# design.net
KiCad netlist of a schematic drawn in Altium Designer
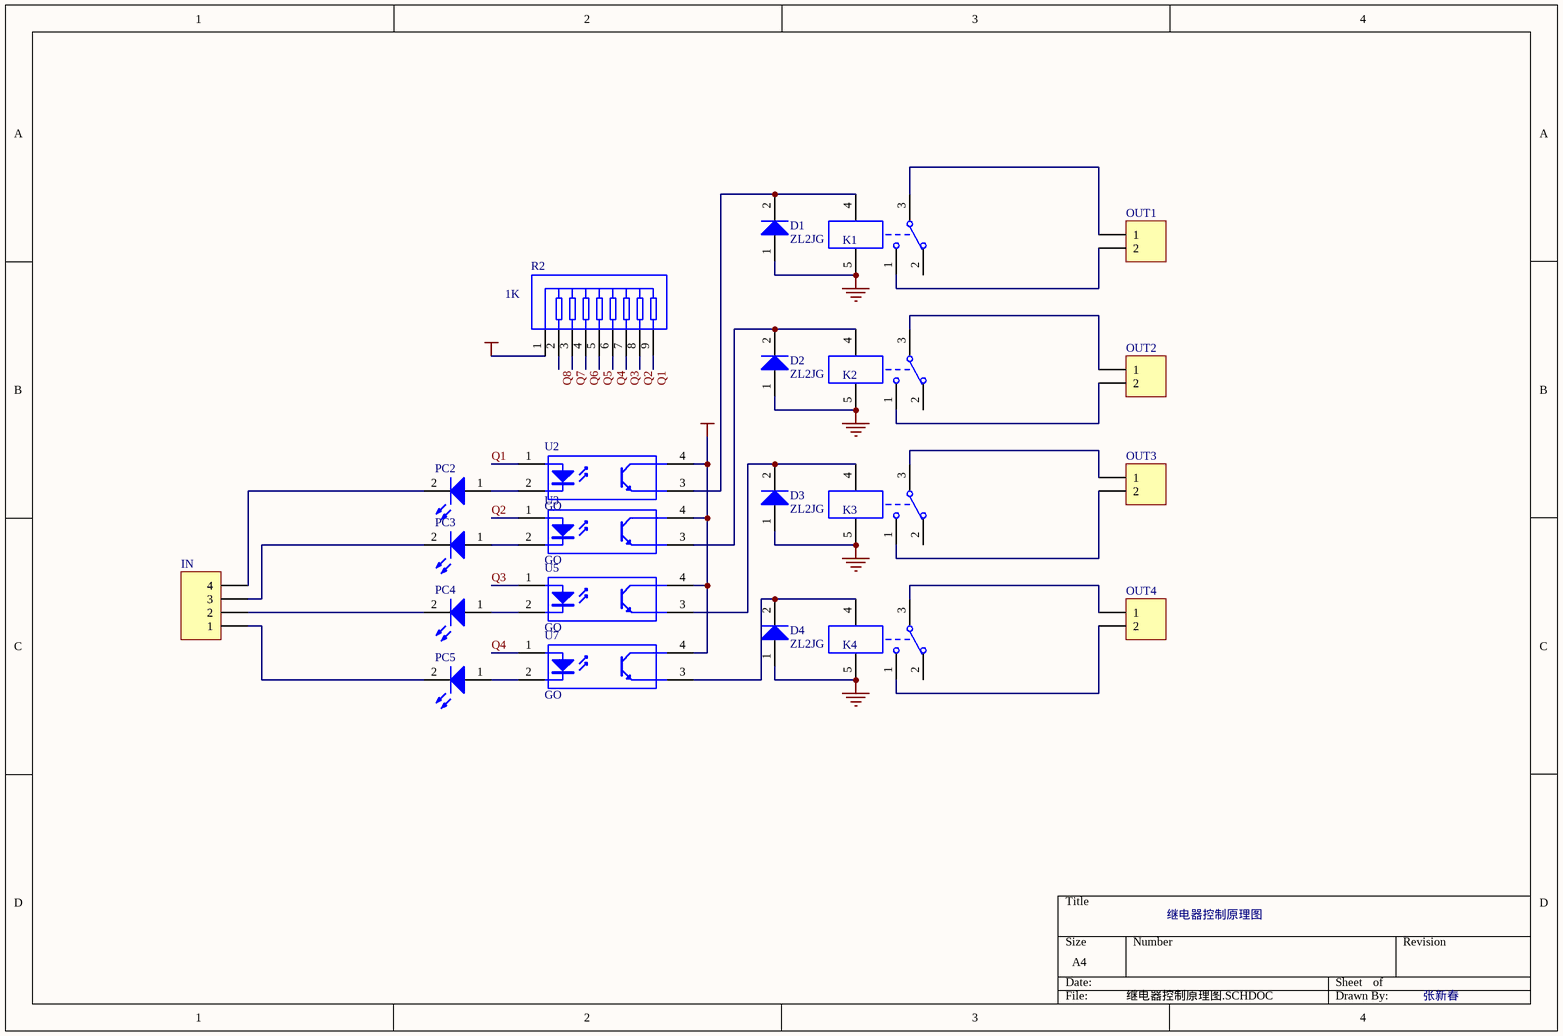
[diagram p0: 继电器控制原理图.SCHDOC]

(export (version "E")
  (design (tool "Eeschema 10.0.6"))
  (components
    (comp (ref "D1")
      (value "ZL2JG")
      (footprint "D-ZL-10")
      (description "整流二极管")
      (fields (field (name "PUBLISHER") "Altium Limited"))
      (libsource (lib "zxcourhc") (part "ZL2JG"))
    )
    (comp (ref "D2")
      (value "ZL2JG")
      (footprint "D-ZL-10")
      (description "整流二极管")
      (fields (field (name "PUBLISHER") "Altium Limited"))
      (libsource (lib "zxcourhc") (part "ZL2JG"))
    )
    (comp (ref "D3")
      (value "ZL2JG")
      (footprint "D-ZL-10")
      (description "整流二极管")
      (fields (field (name "PUBLISHER") "Altium Limited"))
      (libsource (lib "zxcourhc") (part "ZL2JG"))
    )
    (comp (ref "D4")
      (value "ZL2JG")
      (footprint "D-ZL-10")
      (description "整流二极管")
      (fields (field (name "PUBLISHER") "Altium Limited"))
      (libsource (lib "zxcourhc") (part "ZL2JG"))
    )
    (comp (ref "IN")
      (value "Header 4")
      (footprint "HDR1X4")
      (description "Header, 4-Pin")
      (fields (field (name "PUBLISHER") "Altium Limited"))
      (libsource (lib "Miscellaneous Connectors") (part "Header 4"))
    )
    (comp (ref "K1")
      (value "JDQYCK")
      (footprint "JQC-3F/T73")
      (description "继电器——1常开1常闭")
      (fields (field (name "PUBLISHER") "Altium Limited"))
      (libsource (lib "zxcourhc") (part "JDQYCK"))
    )
    (comp (ref "K2")
      (value "JDQYCK")
      (footprint "JQC-3F/T73")
      (description "继电器——1常开1常闭")
      (fields (field (name "PUBLISHER") "Altium Limited"))
      (libsource (lib "zxcourhc") (part "JDQYCK"))
    )
    (comp (ref "K3")
      (value "JDQYCK")
      (footprint "JQC-3F/T73")
      (description "继电器——1常开1常闭")
      (fields (field (name "PUBLISHER") "Altium Limited"))
      (libsource (lib "zxcourhc") (part "JDQYCK"))
    )
    (comp (ref "K4")
      (value "JDQYCK")
      (footprint "JQC-3F/T73")
      (description "继电器——1常开1常闭")
      (fields (field (name "PUBLISHER") "Altium Limited"))
      (libsource (lib "zxcourhc") (part "JDQYCK"))
    )
    (comp (ref "OUT1")
      (value "PZ_2")
      (footprint "DYDZ")
      (description "排针——2")
      (fields (field (name "PUBLISHER") "Altium Limited"))
      (libsource (lib "zxcourhc") (part "PZ_2"))
    )
    (comp (ref "OUT2")
      (value "PZ_2")
      (footprint "DYDZ")
      (description "排针——2")
      (fields (field (name "PUBLISHER") "Altium Limited"))
      (libsource (lib "zxcourhc") (part "PZ_2"))
    )
    (comp (ref "OUT3")
      (value "PZ_2")
      (footprint "DYDZ")
      (description "排针——2")
      (fields (field (name "PUBLISHER") "Altium Limited"))
      (libsource (lib "zxcourhc") (part "PZ_2"))
    )
    (comp (ref "OUT4")
      (value "PZ_2")
      (footprint "DYDZ")
      (description "排针——2")
      (fields (field (name "PUBLISHER") "Altium Limited"))
      (libsource (lib "zxcourhc") (part "PZ_2"))
    )
    (comp (ref "PC2")
      (value "~")
      (footprint "CPDR")
      (description "发光二极管")
      (fields (field (name "PUBLISHER") "Altium Limited"))
      (libsource (lib "zxcourhc") (part "LED"))
    )
    (comp (ref "PC3")
      (value "~")
      (footprint "CPDR")
      (description "发光二极管")
      (fields (field (name "PUBLISHER") "Altium Limited"))
      (libsource (lib "zxcourhc") (part "LED"))
    )
    (comp (ref "PC4")
      (value "~")
      (footprint "CPDR")
      (description "发光二极管")
      (fields (field (name "PUBLISHER") "Altium Limited"))
      (libsource (lib "zxcourhc") (part "LED"))
    )
    (comp (ref "PC5")
      (value "~")
      (footprint "CPDR")
      (description "发光二极管")
      (fields (field (name "PUBLISHER") "Altium Limited"))
      (libsource (lib "zxcourhc") (part "LED"))
    )
    (comp (ref "R2")
      (value "1K")
      (footprint "HDR-10")
      (description "8位排阻")
      (fields (field (name "PUBLISHER") "Altium Limited"))
      (libsource (lib "zxcourhc") (part "Res PZ_8"))
    )
    (comp (ref "U2")
      (value "GO")
      (footprint "DIP-4")
      (description "光耦")
      (fields (field (name "PUBLISHER") "Altium Limited"))
      (libsource (lib "zxcourhc") (part "GO"))
    )
    (comp (ref "U3")
      (value "GO")
      (footprint "DIP-4")
      (description "光耦")
      (fields (field (name "PUBLISHER") "Altium Limited"))
      (libsource (lib "zxcourhc") (part "GO"))
    )
    (comp (ref "U5")
      (value "GO")
      (footprint "DIP-4")
      (description "光耦")
      (fields (field (name "PUBLISHER") "Altium Limited"))
      (libsource (lib "zxcourhc") (part "GO"))
    )
    (comp (ref "U7")
      (value "GO")
      (footprint "DIP-4")
      (description "光耦")
      (fields (field (name "PUBLISHER") "Altium Limited"))
      (libsource (lib "zxcourhc") (part "GO"))
    )
  )
  (nets
    (net (code "1") (name "+12V") (class "Default")
      (node (ref "U2") (pin "4") (pinfunction "C_4") (pintype "passive"))
      (node (ref "U3") (pin "4") (pinfunction "C_4") (pintype "passive"))
      (node (ref "U5") (pin "4") (pinfunction "C_4") (pintype "passive"))
      (node (ref "U7") (pin "4") (pinfunction "C_4") (pintype "passive"))
    )
    (net (code "2") (name "/Q1") (class "Default")
      (node (ref "R2") (pin "9") (pinfunction "9_9") (pintype "passive"))
      (node (ref "U2") (pin "1") (pinfunction "A_1") (pintype "passive"))
    )
    (net (code "3") (name "/Q2") (class "Default")
      (node (ref "R2") (pin "8") (pinfunction "8_8") (pintype "passive"))
      (node (ref "U3") (pin "1") (pinfunction "A_1") (pintype "passive"))
    )
    (net (code "4") (name "/Q3") (class "Default")
      (node (ref "R2") (pin "7") (pinfunction "7_7") (pintype "passive"))
      (node (ref "U5") (pin "1") (pinfunction "A_1") (pintype "passive"))
    )
    (net (code "5") (name "/Q4") (class "Default")
      (node (ref "R2") (pin "6") (pinfunction "6_6") (pintype "passive"))
      (node (ref "U7") (pin "1") (pinfunction "A_1") (pintype "passive"))
    )
    (net (code "6") (name "/Q5") (class "Default")
      (node (ref "R2") (pin "5") (pinfunction "5_5") (pintype "passive"))
    )
    (net (code "7") (name "/Q6") (class "Default")
      (node (ref "R2") (pin "4") (pinfunction "4_4") (pintype "passive"))
    )
    (net (code "8") (name "/Q7") (class "Default")
      (node (ref "R2") (pin "3") (pinfunction "3_3") (pintype "passive"))
    )
    (net (code "9") (name "/Q8") (class "Default")
      (node (ref "R2") (pin "2") (pinfunction "2_2") (pintype "passive"))
    )
    (net (code "10") (name "GND") (class "Default")
      (node (ref "D1") (pin "1") (pinfunction "A_1") (pintype "passive"))
      (node (ref "D2") (pin "1") (pinfunction "A_1") (pintype "passive"))
      (node (ref "D3") (pin "1") (pinfunction "A_1") (pintype "passive"))
      (node (ref "D4") (pin "1") (pinfunction "A_1") (pintype "passive"))
      (node (ref "K1") (pin "5") (pinfunction "5_5") (pintype "passive"))
      (node (ref "K2") (pin "5") (pinfunction "5_5") (pintype "passive"))
      (node (ref "K3") (pin "5") (pinfunction "5_5") (pintype "passive"))
      (node (ref "K4") (pin "5") (pinfunction "5_5") (pintype "passive"))
    )
    (net (code "11") (name "Net-(D1-K)") (class "Default")
      (node (ref "D1") (pin "2") (pinfunction "K_2") (pintype "passive"))
      (node (ref "K1") (pin "4") (pinfunction "4_4") (pintype "passive"))
      (node (ref "U2") (pin "3") (pinfunction "E_3") (pintype "passive"))
    )
    (net (code "12") (name "Net-(D2-K)") (class "Default")
      (node (ref "D2") (pin "2") (pinfunction "K_2") (pintype "passive"))
      (node (ref "K2") (pin "4") (pinfunction "4_4") (pintype "passive"))
      (node (ref "U3") (pin "3") (pinfunction "E_3") (pintype "passive"))
    )
    (net (code "13") (name "Net-(D3-K)") (class "Default")
      (node (ref "D3") (pin "2") (pinfunction "K_2") (pintype "passive"))
      (node (ref "K3") (pin "4") (pinfunction "4_4") (pintype "passive"))
      (node (ref "U5") (pin "3") (pinfunction "E_3") (pintype "passive"))
    )
    (net (code "14") (name "Net-(D4-K)") (class "Default")
      (node (ref "D4") (pin "2") (pinfunction "K_2") (pintype "passive"))
      (node (ref "K4") (pin "4") (pinfunction "4_4") (pintype "passive"))
      (node (ref "U7") (pin "3") (pinfunction "E_3") (pintype "passive"))
    )
    (net (code "15") (name "Net-(K1-Pad1)") (class "Default")
      (node (ref "K1") (pin "1") (pinfunction "1_1") (pintype "passive"))
      (node (ref "OUT1") (pin "2") (pinfunction "2_2") (pintype "passive"))
    )
    (net (code "16") (name "Net-(K1-Pad3)") (class "Default")
      (node (ref "K1") (pin "3") (pinfunction "3_3") (pintype "passive"))
      (node (ref "OUT1") (pin "1") (pinfunction "1_1") (pintype "passive"))
    )
    (net (code "17") (name "Net-(K2-Pad1)") (class "Default")
      (node (ref "K2") (pin "1") (pinfunction "1_1") (pintype "passive"))
      (node (ref "OUT2") (pin "2") (pinfunction "2_2") (pintype "passive"))
    )
    (net (code "18") (name "Net-(K2-Pad3)") (class "Default")
      (node (ref "K2") (pin "3") (pinfunction "3_3") (pintype "passive"))
      (node (ref "OUT2") (pin "1") (pinfunction "1_1") (pintype "passive"))
    )
    (net (code "19") (name "Net-(K3-Pad1)") (class "Default")
      (node (ref "K3") (pin "1") (pinfunction "1_1") (pintype "passive"))
      (node (ref "OUT3") (pin "2") (pinfunction "2_2") (pintype "passive"))
    )
    (net (code "20") (name "Net-(K3-Pad3)") (class "Default")
      (node (ref "K3") (pin "3") (pinfunction "3_3") (pintype "passive"))
      (node (ref "OUT3") (pin "1") (pinfunction "1_1") (pintype "passive"))
    )
    (net (code "21") (name "Net-(K4-Pad1)") (class "Default")
      (node (ref "K4") (pin "1") (pinfunction "1_1") (pintype "passive"))
      (node (ref "OUT4") (pin "2") (pinfunction "2_2") (pintype "passive"))
    )
    (net (code "22") (name "Net-(K4-Pad3)") (class "Default")
      (node (ref "K4") (pin "3") (pinfunction "3_3") (pintype "passive"))
      (node (ref "OUT4") (pin "1") (pinfunction "1_1") (pintype "passive"))
    )
    (net (code "23") (name "Net-(PC2-A)") (class "Default")
      (node (ref "PC2") (pin "1") (pinfunction "A_1") (pintype "passive"))
      (node (ref "U2") (pin "2") (pinfunction "K_2") (pintype "passive"))
    )
    (net (code "24") (name "Net-(PC2-K)") (class "Default")
      (node (ref "IN") (pin "4") (pinfunction "4_4") (pintype "passive"))
      (node (ref "PC2") (pin "2") (pinfunction "K_2") (pintype "passive"))
    )
    (net (code "25") (name "Net-(PC3-A)") (class "Default")
      (node (ref "PC3") (pin "1") (pinfunction "A_1") (pintype "passive"))
      (node (ref "U3") (pin "2") (pinfunction "K_2") (pintype "passive"))
    )
    (net (code "26") (name "Net-(PC3-K)") (class "Default")
      (node (ref "IN") (pin "3") (pinfunction "3_3") (pintype "passive"))
      (node (ref "PC3") (pin "2") (pinfunction "K_2") (pintype "passive"))
    )
    (net (code "27") (name "Net-(PC4-A)") (class "Default")
      (node (ref "PC4") (pin "1") (pinfunction "A_1") (pintype "passive"))
      (node (ref "U5") (pin "2") (pinfunction "K_2") (pintype "passive"))
    )
    (net (code "28") (name "Net-(PC4-K)") (class "Default")
      (node (ref "IN") (pin "2") (pinfunction "2_2") (pintype "passive"))
      (node (ref "PC4") (pin "2") (pinfunction "K_2") (pintype "passive"))
    )
    (net (code "29") (name "Net-(PC5-A)") (class "Default")
      (node (ref "PC5") (pin "1") (pinfunction "A_1") (pintype "passive"))
      (node (ref "U7") (pin "2") (pinfunction "K_2") (pintype "passive"))
    )
    (net (code "30") (name "Net-(PC5-K)") (class "Default")
      (node (ref "IN") (pin "1") (pinfunction "1_1") (pintype "passive"))
      (node (ref "PC5") (pin "2") (pinfunction "K_2") (pintype "passive"))
    )
    (net (code "31") (name "VCC") (class "Default")
      (node (ref "R2") (pin "1") (pinfunction "1_1") (pintype "passive"))
    )
    (net (code "32") (name "unconnected-(K1-Pad2)") (class "Default")
      (node (ref "K1") (pin "2") (pinfunction "2_2") (pintype "passive"))
    )
    (net (code "33") (name "unconnected-(K2-Pad2)") (class "Default")
      (node (ref "K2") (pin "2") (pinfunction "2_2") (pintype "passive"))
    )
    (net (code "34") (name "unconnected-(K3-Pad2)") (class "Default")
      (node (ref "K3") (pin "2") (pinfunction "2_2") (pintype "passive"))
    )
    (net (code "35") (name "unconnected-(K4-Pad2)") (class "Default")
      (node (ref "K4") (pin "2") (pinfunction "2_2") (pintype "passive"))
    )
  )
)
